# MovuinoHealthBandV0_2_7_2-max86141-v0_2_.net
KiCad netlist of a schematic drawn in EAGLE
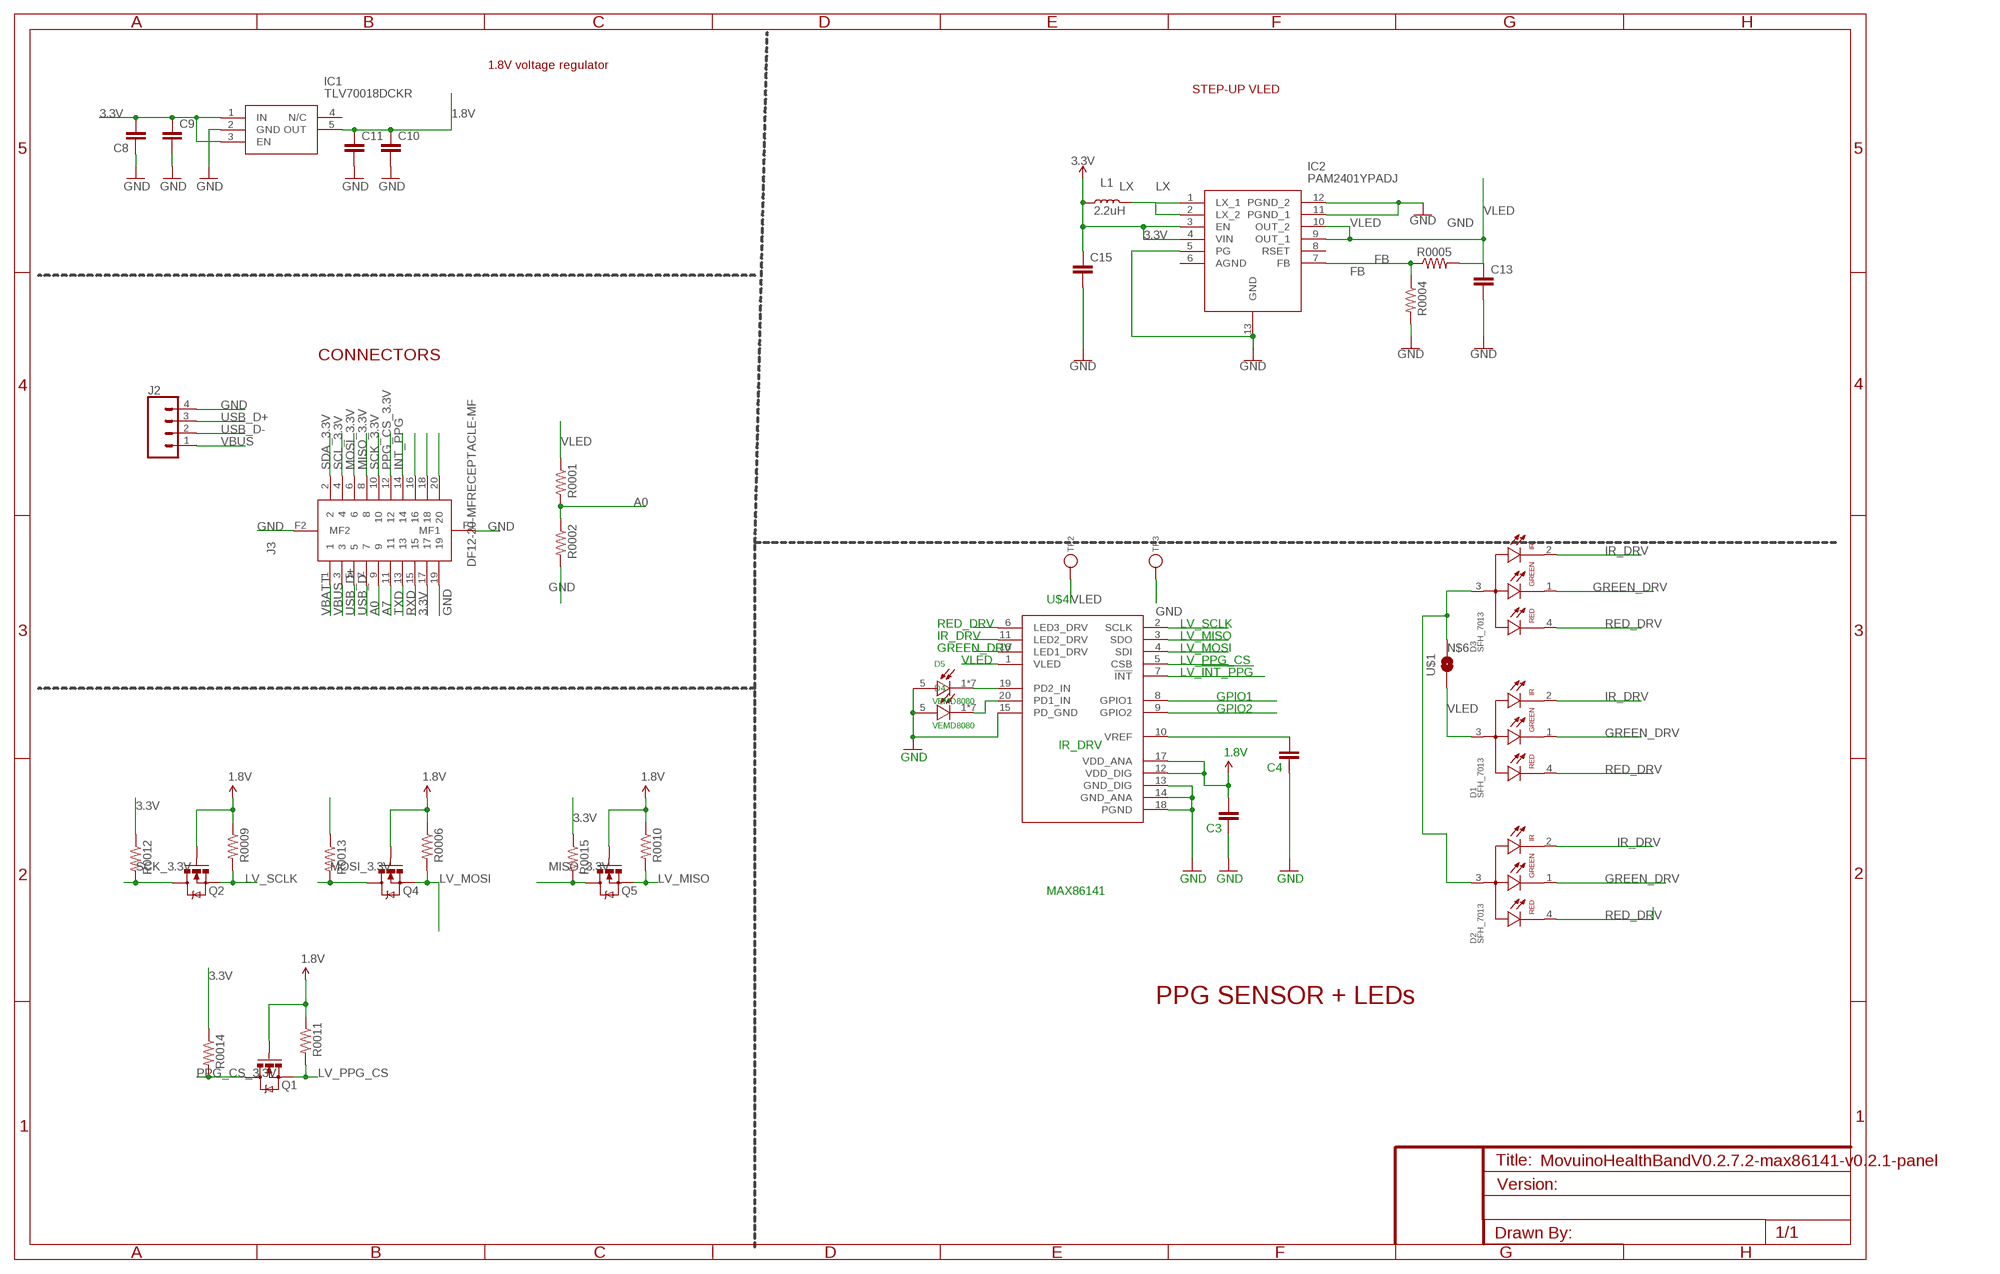
[diagram p0: schematic, sheet 1]

(export (version "E")
  (design (tool "Eeschema 10.0.6"))
  (components
    (comp (ref "C3")
      (value "1uF")
      (footprint "eagle-import:0402-CAP")
      (libsource (lib "eagle-import") (part "CAP0402-CAP"))
    )
    (comp (ref "C4")
      (value "10uF")
      (footprint "eagle-import:0402-CAP")
      (libsource (lib "eagle-import") (part "CAP0402-CAP"))
    )
    (comp (ref "C8")
      (value "10uF")
      (footprint "eagle-import:0402-CAP-SMALL-TDOCU")
      (libsource (lib "eagle-import") (part "CAP0402-CAP-SMALL-TDOCU"))
    )
    (comp (ref "C9")
      (value "0.1uF")
      (footprint "eagle-import:0402-CAP-SMALL-TDOCU")
      (libsource (lib "eagle-import") (part "CAP0402-CAP-SMALL-TDOCU"))
    )
    (comp (ref "C10")
      (value "0.1uF")
      (footprint "eagle-import:0402-CAP-SMALL-TDOCU")
      (libsource (lib "eagle-import") (part "CAP0402-CAP-SMALL-TDOCU"))
    )
    (comp (ref "C11")
      (value "4.7uF")
      (footprint "eagle-import:0402-CAP-SMALL-TDOCU")
      (libsource (lib "eagle-import") (part "CAP0402-CAP-SMALL-TDOCU"))
    )
    (comp (ref "C13")
      (value "22uF")
      (footprint "eagle-import:0402-CAP-SMALL-TDOCU")
      (libsource (lib "eagle-import") (part "CAP0402-CAP-SMALL-TDOCU"))
    )
    (comp (ref "C15")
      (value "10uF")
      (footprint "eagle-import:0402-CAP-SMALL-TDOCU")
      (libsource (lib "eagle-import") (part "CAP0402-CAP-SMALL-TDOCU"))
    )
    (comp (ref "D1")
      (value "SFH_7013")
      (footprint "eagle-import:SFH_7013")
      (fields (field (name "MF") "OSRAM Opto") (field (name "MP") "SFH 7013"))
      (libsource (lib "eagle-import") (part "SFH_7013"))
    )
    (comp (ref "D2")
      (value "SFH_7013")
      (footprint "eagle-import:SFH_7013")
      (fields (field (name "MF") "OSRAM Opto") (field (name "MP") "SFH 7013"))
      (libsource (lib "eagle-import") (part "SFH_7013"))
    )
    (comp (ref "D3")
      (value "SFH_7013")
      (footprint "eagle-import:SFH_7013")
      (fields (field (name "MF") "OSRAM Opto") (field (name "MP") "SFH 7013"))
      (libsource (lib "eagle-import") (part "SFH_7013"))
    )
    (comp (ref "D4")
      (value "VEMD8080")
      (footprint "eagle-import:XDCR_VEMD8080")
      (fields (field (name "MF") "Vishay Semiconductor Opto Division"))
      (libsource (lib "eagle-import") (part "VEMD8080"))
    )
    (comp (ref "D5")
      (value "VEMD8080")
      (footprint "eagle-import:XDCR_VEMD8080")
      (fields (field (name "MF") "Vishay Semiconductor Opto Division"))
      (libsource (lib "eagle-import") (part "VEMD8080"))
    )
    (comp (ref "IC1")
      (value "TLV70018DCKR")
      (footprint "eagle-import:SOT65P210X110-5N")
      (fields (field (name "MOUSER_PART_NUMBER") "595-TLV70018DCKR"))
      (libsource (lib "eagle-import") (part "TLV70018DCKR"))
    )
    (comp (ref "IC2")
      (value "PAM2401YPADJ")
      (footprint "eagle-import:SON45P295X295X60-13N")
      (fields (field (name "MOUSER_PART_NUMBER") "621-PAM2401YPADJ"))
      (libsource (lib "eagle-import") (part "PAM2401YPADJ"))
    )
    (comp (ref "J2")
      (value "CONN_04POGO-2.54")
      (footprint "eagle-import:POGO_2.54_X4")
      (libsource (lib "eagle-import") (part "CONN_04POGO-2.54"))
    )
    (comp (ref "J3")
      (value "DF12-20-MFRECEPTACLE-MF")
      (footprint "eagle-import:DF12-20-DS")
      (fields (field (name "MPN") "DF12-20DS-0.5V(86)"))
      (libsource (lib "eagle-import") (part "DF12-20-MFRECEPTACLE-MF"))
    )
    (comp (ref "L1")
      (value "2.2uH")
      (footprint "eagle-import:INDC2016X100N")
      (fields (field (name "MPN") "LQM2MPN2R2MGHL"))
      (libsource (lib "eagle-import") (part "INDUCTOR"))
    )
    (comp (ref "Q1")
      (value "N-MOSFETBSS138")
      (footprint "eagle-import:SOT23-3")
      (libsource (lib "eagle-import") (part "N-MOSFETBSS138"))
    )
    (comp (ref "Q2")
      (value "N-MOSFETBSS138")
      (footprint "eagle-import:SOT23-3")
      (libsource (lib "eagle-import") (part "N-MOSFETBSS138"))
    )
    (comp (ref "Q4")
      (value "N-MOSFETBSS138")
      (footprint "eagle-import:SOT23-3")
      (libsource (lib "eagle-import") (part "N-MOSFETBSS138"))
    )
    (comp (ref "Q5")
      (value "N-MOSFETBSS138")
      (footprint "eagle-import:SOT23-3")
      (libsource (lib "eagle-import") (part "N-MOSFETBSS138"))
    )
    (comp (ref "R0001")
      (value "4.7K")
      (footprint "eagle-import:0402-RES")
      (fields (field (name "TOLERANCE") "1%"))
      (libsource (lib "eagle-import") (part "RESISTOR0402-RES"))
    )
    (comp (ref "R0002")
      (value "4.7K")
      (footprint "eagle-import:0402-RES")
      (fields (field (name "TOLERANCE") "1%"))
      (libsource (lib "eagle-import") (part "RESISTOR0402-RES"))
    )
    (comp (ref "R0004")
      (value "100K")
      (footprint "eagle-import:0402-RES")
      (fields (field (name "TOLERANCE") "1%"))
      (libsource (lib "eagle-import") (part "RESISTOR0402-RES"))
    )
    (comp (ref "R0005")
      (value "750K")
      (footprint "eagle-import:0402-RES")
      (fields (field (name "TOLERANCE") "1%"))
      (libsource (lib "eagle-import") (part "RESISTOR0402-RES"))
    )
    (comp (ref "R0006")
      (value "4.7K")
      (footprint "eagle-import:0402-RES")
      (fields (field (name "TOLERANCE") "1%"))
      (libsource (lib "eagle-import") (part "RESISTOR0402-RES"))
    )
    (comp (ref "R0009")
      (value "4.7K")
      (footprint "eagle-import:0402-RES")
      (fields (field (name "TOLERANCE") "1%"))
      (libsource (lib "eagle-import") (part "RESISTOR0402-RES"))
    )
    (comp (ref "R0010")
      (value "4.7K")
      (footprint "eagle-import:0402-RES")
      (fields (field (name "TOLERANCE") "1%"))
      (libsource (lib "eagle-import") (part "RESISTOR0402-RES"))
    )
    (comp (ref "R0011")
      (value "4.7K")
      (footprint "eagle-import:0402-RES")
      (fields (field (name "TOLERANCE") "1%"))
      (libsource (lib "eagle-import") (part "RESISTOR0402-RES"))
    )
    (comp (ref "R0012")
      (value "4.7K")
      (footprint "eagle-import:0402-RES")
      (fields (field (name "TOLERANCE") "1%"))
      (libsource (lib "eagle-import") (part "RESISTOR0402-RES"))
    )
    (comp (ref "R0013")
      (value "4.7K")
      (footprint "eagle-import:0402-RES")
      (fields (field (name "TOLERANCE") "1%"))
      (libsource (lib "eagle-import") (part "RESISTOR0402-RES"))
    )
    (comp (ref "R0014")
      (value "4.7K")
      (footprint "eagle-import:0402-RES")
      (fields (field (name "TOLERANCE") "1%"))
      (libsource (lib "eagle-import") (part "RESISTOR0402-RES"))
    )
    (comp (ref "R0015")
      (value "4.7K")
      (footprint "eagle-import:0402-RES")
      (fields (field (name "TOLERANCE") "1%"))
      (libsource (lib "eagle-import") (part "RESISTOR0402-RES"))
    )
    (comp (ref "TP2")
      (value "TESTPOINT1MM-ROUND-CREAM")
      (footprint "eagle-import:TESTPOINT_ROUND_1MM-CREAM")
      (libsource (lib "eagle-import") (part "TESTPOINT1MM-ROUND-CREAM"))
    )
    (comp (ref "TP3")
      (value "TESTPOINT1MM-ROUND-CREAM")
      (footprint "eagle-import:TESTPOINT_ROUND_1MM-CREAM")
      (libsource (lib "eagle-import") (part "TESTPOINT1MM-ROUND-CREAM"))
    )
    (comp (ref "U$1")
      (value "0402-JUMPER")
      (footprint "eagle-import:0402-JUMPER")
      (libsource (lib "eagle-import") (part "0402-JUMPER"))
    )
    (comp (ref "U$4")
      (value "MAX86141")
      (footprint "eagle-import:20_PIN_WLP")
      (libsource (lib "eagle-import") (part "MAX86141"))
    )
  )
  (nets
    (net (code "1") (name "/A0") (class "Default")
      (node (ref "J3") (pin "9") (pinfunction "9_9") (pintype "bidirectional"))
      (node (ref "R0001") (pin "2") (pinfunction "2_2") (pintype "passive"))
      (node (ref "R0002") (pin "1") (pinfunction "1_1") (pintype "passive"))
    )
    (net (code "2") (name "/A7") (class "Default")
      (node (ref "J3") (pin "11") (pinfunction "11_11") (pintype "bidirectional"))
    )
    (net (code "3") (name "/FB") (class "Default")
      (node (ref "IC2") (pin "7") (pinfunction "FB_7") (pintype "bidirectional"))
      (node (ref "R0004") (pin "1") (pinfunction "1_1") (pintype "passive"))
      (node (ref "R0005") (pin "1") (pinfunction "1_1") (pintype "passive"))
    )
    (net (code "4") (name "/GPIO1") (class "Default")
      (node (ref "U$4") (pin "8") (pinfunction "GPIO1_8") (pintype "bidirectional"))
    )
    (net (code "5") (name "/GPIO2") (class "Default")
      (node (ref "U$4") (pin "9") (pinfunction "GPIO2_9") (pintype "bidirectional"))
    )
    (net (code "6") (name "/GREEN_DRV") (class "Default")
      (node (ref "D1") (pin "1") (pinfunction "CATHODE_EMITTER_2_1") (pintype "passive"))
      (node (ref "D2") (pin "1") (pinfunction "CATHODE_EMITTER_2_1") (pintype "passive"))
      (node (ref "D3") (pin "1") (pinfunction "CATHODE_EMITTER_2_1") (pintype "passive"))
      (node (ref "U$4") (pin "16") (pinfunction "LED1_DRV_16") (pintype "bidirectional"))
    )
    (net (code "7") (name "/INT_PPG") (class "Default")
      (node (ref "J3") (pin "14") (pinfunction "14_14") (pintype "bidirectional"))
    )
    (net (code "8") (name "/IR_DRV") (class "Default")
      (node (ref "D1") (pin "2") (pinfunction "CATHODE_EMITTER_3_2") (pintype "passive"))
      (node (ref "D2") (pin "2") (pinfunction "CATHODE_EMITTER_3_2") (pintype "passive"))
      (node (ref "D3") (pin "2") (pinfunction "CATHODE_EMITTER_3_2") (pintype "passive"))
      (node (ref "U$4") (pin "11") (pinfunction "LED2_DRV_11") (pintype "bidirectional"))
    )
    (net (code "9") (name "/LV_MISO") (class "Default")
      (node (ref "Q5") (pin "2") (pinfunction "S_2") (pintype "passive"))
      (node (ref "R0010") (pin "2") (pinfunction "2_2") (pintype "passive"))
      (node (ref "U$4") (pin "3") (pinfunction "SDO_3") (pintype "bidirectional"))
    )
    (net (code "10") (name "/LV_MOSI") (class "Default")
      (node (ref "Q4") (pin "2") (pinfunction "S_2") (pintype "passive"))
      (node (ref "R0006") (pin "2") (pinfunction "2_2") (pintype "passive"))
      (node (ref "U$4") (pin "4") (pinfunction "SDI_4") (pintype "bidirectional"))
    )
    (net (code "11") (name "/LV_PPG_CS") (class "Default")
      (node (ref "Q1") (pin "2") (pinfunction "S_2") (pintype "passive"))
      (node (ref "R0011") (pin "2") (pinfunction "2_2") (pintype "passive"))
      (node (ref "U$4") (pin "5") (pinfunction "CSB_5") (pintype "bidirectional"))
    )
    (net (code "12") (name "/LV_SCLK") (class "Default")
      (node (ref "Q2") (pin "2") (pinfunction "S_2") (pintype "passive"))
      (node (ref "R0009") (pin "2") (pinfunction "2_2") (pintype "passive"))
      (node (ref "U$4") (pin "2") (pinfunction "SCLK_2") (pintype "bidirectional"))
    )
    (net (code "13") (name "/LV_~{INT_PPG}") (class "Default")
      (node (ref "U$4") (pin "7") (pinfunction "~{INT}_7") (pintype "bidirectional"))
    )
    (net (code "14") (name "/LX") (class "Default")
      (node (ref "IC2") (pin "1") (pinfunction "LX_1_1") (pintype "bidirectional"))
      (node (ref "IC2") (pin "2") (pinfunction "LX_2_2") (pintype "bidirectional"))
      (node (ref "L1") (pin "2") (pinfunction "2_2") (pintype "passive"))
    )
    (net (code "15") (name "/MISO_3.3V") (class "Default")
      (node (ref "J3") (pin "8") (pinfunction "8_8") (pintype "bidirectional"))
      (node (ref "Q5") (pin "3") (pinfunction "D_3") (pintype "passive"))
      (node (ref "R0015") (pin "2") (pinfunction "2_2") (pintype "passive"))
    )
    (net (code "16") (name "/MOSI_3.3V") (class "Default")
      (node (ref "J3") (pin "6") (pinfunction "6_6") (pintype "bidirectional"))
      (node (ref "Q4") (pin "3") (pinfunction "D_3") (pintype "passive"))
      (node (ref "R0013") (pin "2") (pinfunction "2_2") (pintype "passive"))
    )
    (net (code "17") (name "/N$6") (class "Default")
      (node (ref "D2") (pin "3") (pinfunction "ANODE_EMITTER_1/2/3_3") (pintype "passive"))
      (node (ref "D3") (pin "3") (pinfunction "ANODE_EMITTER_1/2/3_3") (pintype "passive"))
      (node (ref "U$1") (pin "2") (pinfunction "2_2") (pintype "bidirectional"))
    )
    (net (code "18") (name "/PPG_CS_3.3V") (class "Default")
      (node (ref "J3") (pin "12") (pinfunction "12_12") (pintype "bidirectional"))
      (node (ref "Q1") (pin "3") (pinfunction "D_3") (pintype "passive"))
      (node (ref "R0014") (pin "2") (pinfunction "2_2") (pintype "passive"))
    )
    (net (code "19") (name "/RED_DRV") (class "Default")
      (node (ref "D1") (pin "4") (pinfunction "CATHODE_EMITTER_1_4") (pintype "passive"))
      (node (ref "D2") (pin "4") (pinfunction "CATHODE_EMITTER_1_4") (pintype "passive"))
      (node (ref "D3") (pin "4") (pinfunction "CATHODE_EMITTER_1_4") (pintype "passive"))
      (node (ref "U$4") (pin "6") (pinfunction "LED3_DRV_6") (pintype "bidirectional"))
    )
    (net (code "20") (name "/RXD") (class "Default")
      (node (ref "J3") (pin "15") (pinfunction "15_15") (pintype "bidirectional"))
    )
    (net (code "21") (name "/SCK_3.3V") (class "Default")
      (node (ref "J3") (pin "10") (pinfunction "10_10") (pintype "bidirectional"))
      (node (ref "Q2") (pin "3") (pinfunction "D_3") (pintype "passive"))
      (node (ref "R0012") (pin "2") (pinfunction "2_2") (pintype "passive"))
    )
    (net (code "22") (name "/SCL_3.3V") (class "Default")
      (node (ref "J3") (pin "4") (pinfunction "4_4") (pintype "bidirectional"))
    )
    (net (code "23") (name "/SDA_3.3V") (class "Default")
      (node (ref "J3") (pin "2") (pinfunction "2_2") (pintype "bidirectional"))
    )
    (net (code "24") (name "/TXD") (class "Default")
      (node (ref "J3") (pin "13") (pinfunction "13_13") (pintype "bidirectional"))
    )
    (net (code "25") (name "/USB_D+") (class "Default")
      (node (ref "J2") (pin "3") (pinfunction "3_3") (pintype "passive"))
      (node (ref "J3") (pin "5") (pinfunction "5_5") (pintype "bidirectional"))
    )
    (net (code "26") (name "/USB_D-") (class "Default")
      (node (ref "J2") (pin "2") (pinfunction "2_2") (pintype "passive"))
      (node (ref "J3") (pin "7") (pinfunction "7_7") (pintype "bidirectional"))
    )
    (net (code "27") (name "/VBATT") (class "Default")
      (node (ref "J3") (pin "1") (pinfunction "1_1") (pintype "bidirectional"))
    )
    (net (code "28") (name "/VBUS") (class "Default")
      (node (ref "J2") (pin "1") (pinfunction "1_1") (pintype "passive"))
      (node (ref "J3") (pin "3") (pinfunction "3_3") (pintype "bidirectional"))
    )
    (net (code "29") (name "/VLED") (class "Default")
      (node (ref "C13") (pin "1") (pinfunction "1_1") (pintype "passive"))
      (node (ref "D1") (pin "3") (pinfunction "ANODE_EMITTER_1/2/3_3") (pintype "passive"))
      (node (ref "IC2") (pin "10") (pinfunction "OUT_2_10") (pintype "bidirectional"))
      (node (ref "IC2") (pin "9") (pinfunction "OUT_1_9") (pintype "bidirectional"))
      (node (ref "R0001") (pin "1") (pinfunction "1_1") (pintype "passive"))
      (node (ref "R0005") (pin "2") (pinfunction "2_2") (pintype "passive"))
      (node (ref "TP2") (pin "P$1") (pinfunction "P$1_P$1") (pintype "bidirectional"))
      (node (ref "U$1") (pin "1") (pinfunction "1_1") (pintype "bidirectional"))
      (node (ref "U$4") (pin "1") (pinfunction "VLED_1") (pintype "bidirectional"))
    )
    (net (code "30") (name "1.8V") (class "Default")
      (node (ref "C10") (pin "1") (pinfunction "1_1") (pintype "passive"))
      (node (ref "C11") (pin "1") (pinfunction "1_1") (pintype "passive"))
      (node (ref "C3") (pin "2") (pinfunction "2_2") (pintype "passive"))
      (node (ref "IC1") (pin "5") (pinfunction "OUT_5") (pintype "bidirectional"))
      (node (ref "Q1") (pin "1") (pinfunction "G_1") (pintype "passive"))
      (node (ref "Q2") (pin "1") (pinfunction "G_1") (pintype "passive"))
      (node (ref "Q4") (pin "1") (pinfunction "G_1") (pintype "passive"))
      (node (ref "Q5") (pin "1") (pinfunction "G_1") (pintype "passive"))
      (node (ref "R0006") (pin "1") (pinfunction "1_1") (pintype "passive"))
      (node (ref "R0009") (pin "1") (pinfunction "1_1") (pintype "passive"))
      (node (ref "R0010") (pin "1") (pinfunction "1_1") (pintype "passive"))
      (node (ref "R0011") (pin "1") (pinfunction "1_1") (pintype "passive"))
      (node (ref "U$4") (pin "12") (pinfunction "VDD_DIG_12") (pintype "bidirectional"))
      (node (ref "U$4") (pin "17") (pinfunction "VDD_ANA_17") (pintype "bidirectional"))
    )
    (net (code "31") (name "3.3V") (class "Default")
      (node (ref "C15") (pin "1") (pinfunction "1_1") (pintype "passive"))
      (node (ref "C8") (pin "2") (pinfunction "2_2") (pintype "passive"))
      (node (ref "C9") (pin "1") (pinfunction "1_1") (pintype "passive"))
      (node (ref "IC1") (pin "1") (pinfunction "IN_1") (pintype "bidirectional"))
      (node (ref "IC1") (pin "3") (pinfunction "EN_3") (pintype "bidirectional"))
      (node (ref "IC2") (pin "3") (pinfunction "EN_3") (pintype "bidirectional"))
      (node (ref "IC2") (pin "4") (pinfunction "VIN_4") (pintype "bidirectional"))
      (node (ref "J3") (pin "17") (pinfunction "17_17") (pintype "bidirectional"))
      (node (ref "L1") (pin "1") (pinfunction "1_1") (pintype "passive"))
      (node (ref "R0012") (pin "1") (pinfunction "1_1") (pintype "passive"))
      (node (ref "R0013") (pin "1") (pinfunction "1_1") (pintype "passive"))
      (node (ref "R0014") (pin "1") (pinfunction "1_1") (pintype "passive"))
      (node (ref "R0015") (pin "1") (pinfunction "1_1") (pintype "passive"))
    )
    (net (code "32") (name "GND") (class "Default")
      (node (ref "C10") (pin "2") (pinfunction "2_2") (pintype "passive"))
      (node (ref "C11") (pin "2") (pinfunction "2_2") (pintype "passive"))
      (node (ref "C13") (pin "2") (pinfunction "2_2") (pintype "passive"))
      (node (ref "C15") (pin "2") (pinfunction "2_2") (pintype "passive"))
      (node (ref "C3") (pin "1") (pinfunction "1_1") (pintype "passive"))
      (node (ref "C4") (pin "1") (pinfunction "1_1") (pintype "passive"))
      (node (ref "C8") (pin "1") (pinfunction "1_1") (pintype "passive"))
      (node (ref "C9") (pin "2") (pinfunction "2_2") (pintype "passive"))
      (node (ref "D4") (pin "5") (pinfunction "A_5") (pintype "passive"))
      (node (ref "D5") (pin "5") (pinfunction "A_5") (pintype "passive"))
      (node (ref "IC1") (pin "2") (pinfunction "GND_2") (pintype "bidirectional"))
      (node (ref "IC2") (pin "11") (pinfunction "PGND_1_11") (pintype "bidirectional"))
      (node (ref "IC2") (pin "12") (pinfunction "PGND_2_12") (pintype "bidirectional"))
      (node (ref "IC2") (pin "13") (pinfunction "GND_13") (pintype "bidirectional"))
      (node (ref "IC2") (pin "5") (pinfunction "PG_5") (pintype "bidirectional"))
      (node (ref "J2") (pin "4") (pinfunction "4_4") (pintype "passive"))
      (node (ref "J3") (pin "19") (pinfunction "19_19") (pintype "bidirectional"))
      (node (ref "J3") (pin "F1") (pinfunction "MF1_F1") (pintype "bidirectional"))
      (node (ref "J3") (pin "F2") (pinfunction "MF2_F2") (pintype "bidirectional"))
      (node (ref "R0002") (pin "2") (pinfunction "2_2") (pintype "passive"))
      (node (ref "R0004") (pin "2") (pinfunction "2_2") (pintype "passive"))
      (node (ref "TP3") (pin "P$1") (pinfunction "P$1_P$1") (pintype "bidirectional"))
      (node (ref "U$4") (pin "13") (pinfunction "GND_DIG_13") (pintype "bidirectional"))
      (node (ref "U$4") (pin "14") (pinfunction "GND_ANA_14") (pintype "bidirectional"))
      (node (ref "U$4") (pin "15") (pinfunction "PD_GND_15") (pintype "bidirectional"))
      (node (ref "U$4") (pin "18") (pinfunction "PGND_18") (pintype "bidirectional"))
    )
    (net (code "33") (name "Net-(U$4-PD1_IN)") (class "Default")
      (node (ref "D4") (pin "1") (pinfunction "C_1") (pintype "passive"))
      (node (ref "D4") (pin "2") (pinfunction "C_2") (pintype "passive"))
      (node (ref "D4") (pin "3") (pinfunction "C_3") (pintype "passive"))
      (node (ref "D4") (pin "4") (pinfunction "C_4") (pintype "passive"))
      (node (ref "D4") (pin "6") (pinfunction "C_6") (pintype "passive"))
      (node (ref "D4") (pin "7") (pinfunction "C_7") (pintype "passive"))
      (node (ref "D4") (pin "8") (pinfunction "C_8") (pintype "passive"))
      (node (ref "U$4") (pin "20") (pinfunction "PD1_IN_20") (pintype "bidirectional"))
    )
    (net (code "34") (name "Net-(U$4-PD2_IN)") (class "Default")
      (node (ref "D5") (pin "1") (pinfunction "C_1") (pintype "passive"))
      (node (ref "D5") (pin "2") (pinfunction "C_2") (pintype "passive"))
      (node (ref "D5") (pin "3") (pinfunction "C_3") (pintype "passive"))
      (node (ref "D5") (pin "4") (pinfunction "C_4") (pintype "passive"))
      (node (ref "D5") (pin "6") (pinfunction "C_6") (pintype "passive"))
      (node (ref "D5") (pin "7") (pinfunction "C_7") (pintype "passive"))
      (node (ref "D5") (pin "8") (pinfunction "C_8") (pintype "passive"))
      (node (ref "U$4") (pin "19") (pinfunction "PD2_IN_19") (pintype "bidirectional"))
    )
    (net (code "35") (name "Net-(U$4-VREF)") (class "Default")
      (node (ref "C4") (pin "2") (pinfunction "2_2") (pintype "passive"))
      (node (ref "U$4") (pin "10") (pinfunction "VREF_10") (pintype "bidirectional"))
    )
    (net (code "36") (name "unconnected-(IC1-N{slash}C-Pad4)") (class "Default")
      (node (ref "IC1") (pin "4") (pinfunction "N/C_4") (pintype "no_connect"))
    )
    (net (code "37") (name "unconnected-(IC2-AGND-Pad6)") (class "Default")
      (node (ref "IC2") (pin "6") (pinfunction "AGND_6") (pintype "bidirectional"))
    )
    (net (code "38") (name "unconnected-(IC2-RSET-Pad8)") (class "Default")
      (node (ref "IC2") (pin "8") (pinfunction "RSET_8") (pintype "bidirectional"))
    )
    (net (code "39") (name "unconnected-(J3-Pad16)") (class "Default")
      (node (ref "J3") (pin "16") (pinfunction "16_16") (pintype "bidirectional"))
    )
    (net (code "40") (name "unconnected-(J3-Pad18)") (class "Default")
      (node (ref "J3") (pin "18") (pinfunction "18_18") (pintype "bidirectional"))
    )
    (net (code "41") (name "unconnected-(J3-Pad20)") (class "Default")
      (node (ref "J3") (pin "20") (pinfunction "20_20") (pintype "bidirectional"))
    )
  )
)
